# MCU.net
KiCad netlist of a schematic drawn in Altium Designer
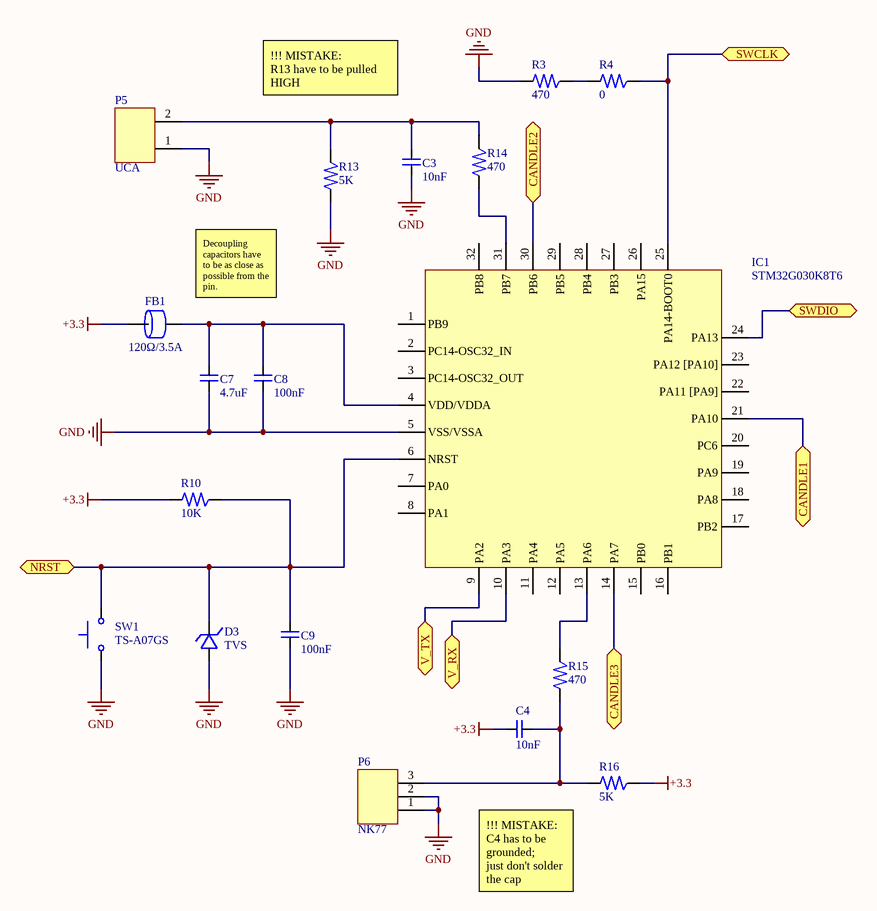
[diagram p0: MCU.SchDoc]

(export (version "E")
  (design (tool "Eeschema 10.0.6"))
  (components
    (comp (ref "C3")
      (value "10nF")
      (footprint "SMT_CAP_0805(2012)_X5R-KYOCERA")
      (description "Multilayer Ceramic Capacitor 0805(2012) KYOCERA AVX 100nF 08055D104KAT2A 50VDC X5R")
      (libsource (lib "SMT_CAP_0805(2012)_X5R-KYOCERA") (part "SMT_CAP_0805(2012)_X5R-KYOCERA"))
    )
    (comp (ref "C4")
      (value "10nF")
      (footprint "SMT_CAP_0805(2012)_X5R-KYOCERA")
      (description "Multilayer Ceramic Capacitor 0805(2012) KYOCERA AVX 100nF 08055D104KAT2A 50VDC X5R")
      (libsource (lib "SMT_CAP_0805(2012)_X5R-KYOCERA") (part "SMT_CAP_0805(2012)_X5R-KYOCERA"))
    )
    (comp (ref "C7")
      (value "4.7uF")
      (footprint "SMT_CAP_1206(3216)_MLCC-KEMET")
      (description "Multilayer Ceramic Capacitor MLCC 1206(3216) KEMET(Yageo) 4.7uF C1206C475K5RACTU 50VDC X7R")
      (libsource (lib "SMT_CAP_1206(3216)_MLCC-KEMET") (part "SMT_CAP_1206(3216)_MLCC-KEMET"))
    )
    (comp (ref "C8")
      (value "100nF")
      (footprint "SMT_CAP_0805(2012)_MLCC-KYOCERA")
      (description "Multilayer Ceramic Capacitor MLCC 1206(3216) KYOCERA AVX 100nF 08055C104JAT2A 50VDC X7R")
      (libsource (lib "SMT_CAP_0805(2012)_MLCC-KYOCERA") (part "SMT_CAP_0805(2012)_MLCC-KYOCERA"))
    )
    (comp (ref "C9")
      (value "100nF")
      (footprint "SMT_CAP_0805(2012)_X5R-KYOCERA")
      (description "Multilayer Ceramic Capacitor 0805(2012) KYOCERA AVX 100nF 08055D104KAT2A 50VDC X5R")
      (libsource (lib "SMT_CAP_0805(2012)_X5R-KYOCERA") (part "SMT_CAP_0805(2012)_X5R-KYOCERA"))
    )
    (comp (ref "D3")
      (value "TVS")
      (footprint "SMT_DIODE_TVS_SOD-323")
      (description "Diode TVS Semtech Vwr=3.3V Vcl=15.7 ESD=30kV Ip=36A RCLAMP03301H.C")
      (libsource (lib "SMT_DIODE_TVS_SOD-323") (part "SMT_DIODE_TVS_SOD-323"))
    )
    (comp (ref "FB1")
      (value "120Ω/3.5A")
      (footprint "SMT_FERR_BEAD_MODEL_1206(3216)_MURATA")
      (description "SMT MURATA Ferrite Bead MODEL 1206(3216) BLM31PG121SN1L *Ω/*mA")
      (libsource (lib "SMT_FERR_BEAD_MODEL_1206(3216)_MURATA") (part "SMT_FERR_BEAD_MODEL_1206(3216)_MURATA"))
    )
    (comp (ref "IC1")
      (value "STM32G030K8T6")
      (footprint "SMT_STM32G030K8T6_IC")
      (description "STM32G030K8T6 Cortex-M0+ Flash=64Kbytes RAM=8Kbyte LQFP-32")
      (libsource (lib "SMT_STM32G030K8T6_IC") (part "SMT_STM32G030K8T6_IC"))
    )
    (comp (ref "P5")
      (value "UCA")
      (footprint "THT_CON_WAFER_2P_2317SJ-02-K0")
      (description "Connector Wafer 2-Pins Pitch-2.5mm Straight_Pins NELTRON 2317SJ-02-K0")
      (libsource (lib "THT_CON_WAFER_3P_2317SJ-02-K0") (part "THT_CON_WAFER_2P_2317SJ-02-K0"))
    )
    (comp (ref "P6")
      (value "NK77")
      (footprint "THT_CON_WAFER_3P_2317SJ-03-K0")
      (description "Connector Wafer 3-Pins Pitch-2.5mm Straight_Pins NELTRON 2317SJ-03-K0")
      (libsource (lib "THT_CON_WAFER_3P_2317SJ-03-K0") (part "THT_CON_WAFER_3P_2317SJ-03-K0"))
    )
    (comp (ref "R3")
      (value "470")
      (footprint "SMT_RES_0805(2012)")
      (description "0805(2012) Resistor 1/4-1/8W 150V 2A")
      (libsource (lib "SMT_RES_0805(2012)") (part "SMT_RES_0805(2012)"))
    )
    (comp (ref "R4")
      (value "0")
      (footprint "SMT_RES_0805(2012)")
      (description "0805(2012) Resistor 1/4-1/8W 150V 2A")
      (libsource (lib "SMT_RES_0805(2012)") (part "SMT_RES_0805(2012)"))
    )
    (comp (ref "R10")
      (value "10K")
      (footprint "SMT_RES_0805(2012)")
      (description "0805(2012) Resistor 1/4-1/8W 150V 2A")
      (libsource (lib "SMT_RES_0805(2012)") (part "SMT_RES_0805(2012)"))
    )
    (comp (ref "R13")
      (value "5K")
      (footprint "SMT_RES_0805(2012)")
      (description "0805(2012) Resistor 1/4-1/8W 150V 2A")
      (libsource (lib "SMT_RES_0805(2012)") (part "SMT_RES_0805(2012)"))
    )
    (comp (ref "R14")
      (value "470")
      (footprint "SMT_RES_0805(2012)")
      (description "0805(2012) Resistor 1/4-1/8W 150V 2A")
      (libsource (lib "SMT_RES_0805(2012)") (part "SMT_RES_0805(2012)"))
    )
    (comp (ref "R15")
      (value "470")
      (footprint "SMT_RES_0805(2012)")
      (description "0805(2012) Resistor 1/4-1/8W 150V 2A")
      (libsource (lib "SMT_RES_0805(2012)") (part "SMT_RES_0805(2012)"))
    )
    (comp (ref "R16")
      (value "5K")
      (footprint "SMT_RES_0805(2012)")
      (description "0805(2012) Resistor 1/4-1/8W 150V 2A")
      (libsource (lib "SMT_RES_0805(2012)") (part "SMT_RES_0805(2012)"))
    )
    (comp (ref "SW1")
      (value "TS-A07GS")
      (footprint "SMT_TSW-A07GS")
      (description "Tactile Switch TS-A07GS 50mA 12V")
      (libsource (lib "SMT_TSW-A07GS") (part "SMT_TSW-A07GS"))
    )
  )
  (nets
    (net (code "1") (name "+3.3") (class "Default")
      (node (ref "C4") (pin "2") (pinfunction "2_2") (pintype "passive"))
      (node (ref "FB1") (pin "1") (pinfunction "1_1") (pintype "passive"))
      (node (ref "R10") (pin "1") (pinfunction "1_1") (pintype "passive"))
      (node (ref "R16") (pin "2") (pinfunction "2_2") (pintype "passive"))
    )
    (net (code "2") (name "/CANDLE1") (class "Default")
      (node (ref "IC1") (pin "21") (pinfunction "PA10_21") (pintype "passive"))
    )
    (net (code "3") (name "/CANDLE2") (class "Default")
      (node (ref "IC1") (pin "30") (pinfunction "PB6_30") (pintype "passive"))
    )
    (net (code "4") (name "/CANDLE3") (class "Default")
      (node (ref "IC1") (pin "14") (pinfunction "PA7_14") (pintype "passive"))
    )
    (net (code "5") (name "/NRST") (class "Default")
      (node (ref "C9") (pin "2") (pinfunction "2_2") (pintype "passive"))
      (node (ref "D3") (pin "1") (pinfunction "1_1") (pintype "passive"))
      (node (ref "IC1") (pin "6") (pinfunction "NRST_6") (pintype "passive"))
      (node (ref "R10") (pin "2") (pinfunction "2_2") (pintype "passive"))
      (node (ref "SW1") (pin "2") (pinfunction "2_2") (pintype "passive"))
    )
    (net (code "6") (name "/SWCLK") (class "Default")
      (node (ref "IC1") (pin "25") (pinfunction "PA14-BOOT0_25") (pintype "passive"))
      (node (ref "R4") (pin "2") (pinfunction "2_2") (pintype "passive"))
    )
    (net (code "7") (name "/SWDIO") (class "Default")
      (node (ref "IC1") (pin "24") (pinfunction "PA13_24") (pintype "passive"))
    )
    (net (code "8") (name "/V_RX") (class "Default")
      (node (ref "IC1") (pin "10") (pinfunction "PA3_10") (pintype "passive"))
    )
    (net (code "9") (name "/V_TX") (class "Default")
      (node (ref "IC1") (pin "9") (pinfunction "PA2_9") (pintype "passive"))
    )
    (net (code "10") (name "GND") (class "Default")
      (node (ref "C3") (pin "2") (pinfunction "2_2") (pintype "passive"))
      (node (ref "C7") (pin "1") (pinfunction "1_1") (pintype "passive"))
      (node (ref "C8") (pin "2") (pinfunction "2_2") (pintype "passive"))
      (node (ref "C9") (pin "1") (pinfunction "1_1") (pintype "passive"))
      (node (ref "D3") (pin "2") (pinfunction "2_2") (pintype "passive"))
      (node (ref "IC1") (pin "5") (pinfunction "VSS/VSSA_5") (pintype "passive"))
      (node (ref "P5") (pin "1") (pintype "passive"))
      (node (ref "P6") (pin "1") (pinfunction "PB9_1") (pintype "passive"))
      (node (ref "P6") (pin "2") (pinfunction "PB10_2") (pintype "passive"))
      (node (ref "R13") (pin "1") (pinfunction "1_1") (pintype "passive"))
      (node (ref "R3") (pin "1") (pinfunction "1_1") (pintype "passive"))
      (node (ref "SW1") (pin "1") (pinfunction "1_1") (pintype "passive"))
    )
    (net (code "11") (name "Net-(C3-Pad1)") (class "Default")
      (node (ref "C3") (pin "1") (pinfunction "1_1") (pintype "passive"))
      (node (ref "P5") (pin "2") (pintype "passive"))
      (node (ref "R13") (pin "2") (pinfunction "2_2") (pintype "passive"))
      (node (ref "R14") (pin "2") (pinfunction "2_2") (pintype "passive"))
    )
    (net (code "12") (name "Net-(IC1-PA6)") (class "Default")
      (node (ref "IC1") (pin "13") (pinfunction "PA6_13") (pintype "passive"))
      (node (ref "R15") (pin "2") (pinfunction "2_2") (pintype "passive"))
    )
    (net (code "13") (name "Net-(IC1-PB7)") (class "Default")
      (node (ref "IC1") (pin "31") (pinfunction "PB7_31") (pintype "passive"))
      (node (ref "R14") (pin "1") (pinfunction "1_1") (pintype "passive"))
    )
    (net (code "14") (name "Net-(IC1-VDD{slash}VDDA)") (class "Default")
      (node (ref "C7") (pin "2") (pinfunction "2_2") (pintype "passive"))
      (node (ref "C8") (pin "1") (pinfunction "1_1") (pintype "passive"))
      (node (ref "FB1") (pin "2") (pinfunction "2_2") (pintype "passive"))
      (node (ref "IC1") (pin "4") (pinfunction "VDD/VDDA_4") (pintype "passive"))
    )
    (net (code "15") (name "Net-(P6-PB11)") (class "Default")
      (node (ref "C4") (pin "1") (pinfunction "1_1") (pintype "passive"))
      (node (ref "P6") (pin "3") (pinfunction "PB11_3") (pintype "passive"))
      (node (ref "R15") (pin "1") (pinfunction "1_1") (pintype "passive"))
      (node (ref "R16") (pin "1") (pinfunction "1_1") (pintype "passive"))
    )
    (net (code "16") (name "Net-(R3-Pad2)") (class "Default")
      (node (ref "R3") (pin "2") (pinfunction "2_2") (pintype "passive"))
      (node (ref "R4") (pin "1") (pinfunction "1_1") (pintype "passive"))
    )
    (net (code "17") (name "unconnected-(IC1-PA0-Pad7)") (class "Default")
      (node (ref "IC1") (pin "7") (pinfunction "PA0_7") (pintype "passive"))
    )
    (net (code "18") (name "unconnected-(IC1-PA1-Pad8)") (class "Default")
      (node (ref "IC1") (pin "8") (pinfunction "PA1_8") (pintype "passive"))
    )
    (net (code "19") (name "unconnected-(IC1-PA4-Pad11)") (class "Default")
      (node (ref "IC1") (pin "11") (pinfunction "PA4_11") (pintype "passive"))
    )
    (net (code "20") (name "unconnected-(IC1-PA5-Pad12)") (class "Default")
      (node (ref "IC1") (pin "12") (pinfunction "PA5_12") (pintype "passive"))
    )
    (net (code "21") (name "unconnected-(IC1-PA8-Pad18)") (class "Default")
      (node (ref "IC1") (pin "18") (pinfunction "PA8_18") (pintype "passive"))
    )
    (net (code "22") (name "unconnected-(IC1-PA9-Pad19)") (class "Default")
      (node (ref "IC1") (pin "19") (pinfunction "PA9_19") (pintype "passive"))
    )
    (net (code "23") (name "unconnected-(IC1-PA11_[PA9]-Pad22)") (class "Default")
      (node (ref "IC1") (pin "22") (pinfunction "PA11_[PA9]_22") (pintype "passive"))
    )
    (net (code "24") (name "unconnected-(IC1-PA12_[PA10]-Pad23)") (class "Default")
      (node (ref "IC1") (pin "23") (pinfunction "PA12_[PA10]_23") (pintype "passive"))
    )
    (net (code "25") (name "unconnected-(IC1-PA15-Pad26)") (class "Default")
      (node (ref "IC1") (pin "26") (pinfunction "PA15_26") (pintype "passive"))
    )
    (net (code "26") (name "unconnected-(IC1-PB0-Pad15)") (class "Default")
      (node (ref "IC1") (pin "15") (pinfunction "PB0_15") (pintype "passive"))
    )
    (net (code "27") (name "unconnected-(IC1-PB1-Pad16)") (class "Default")
      (node (ref "IC1") (pin "16") (pinfunction "PB1_16") (pintype "passive"))
    )
    (net (code "28") (name "unconnected-(IC1-PB2-Pad17)") (class "Default")
      (node (ref "IC1") (pin "17") (pinfunction "PB2_17") (pintype "passive"))
    )
    (net (code "29") (name "unconnected-(IC1-PB3-Pad27)") (class "Default")
      (node (ref "IC1") (pin "27") (pinfunction "PB3_27") (pintype "passive"))
    )
    (net (code "30") (name "unconnected-(IC1-PB4-Pad28)") (class "Default")
      (node (ref "IC1") (pin "28") (pinfunction "PB4_28") (pintype "passive"))
    )
    (net (code "31") (name "unconnected-(IC1-PB5-Pad29)") (class "Default")
      (node (ref "IC1") (pin "29") (pinfunction "PB5_29") (pintype "passive"))
    )
    (net (code "32") (name "unconnected-(IC1-PB8-Pad32)") (class "Default")
      (node (ref "IC1") (pin "32") (pinfunction "PB8_32") (pintype "passive"))
    )
    (net (code "33") (name "unconnected-(IC1-PB9-Pad1)") (class "Default")
      (node (ref "IC1") (pin "1") (pinfunction "PB9_1") (pintype "passive"))
    )
    (net (code "34") (name "unconnected-(IC1-PC6-Pad20)") (class "Default")
      (node (ref "IC1") (pin "20") (pinfunction "PC6_20") (pintype "passive"))
    )
    (net (code "35") (name "unconnected-(IC1-PC14-OSC32_IN-Pad2)") (class "Default")
      (node (ref "IC1") (pin "2") (pinfunction "PC14-OSC32_IN_2") (pintype "passive"))
    )
    (net (code "36") (name "unconnected-(IC1-PC14-OSC32_OUT-Pad3)") (class "Default")
      (node (ref "IC1") (pin "3") (pinfunction "PC14-OSC32_OUT_3") (pintype "passive"))
    )
  )
)
